# PointController.net
KiCad netlist of a schematic drawn in EAGLE
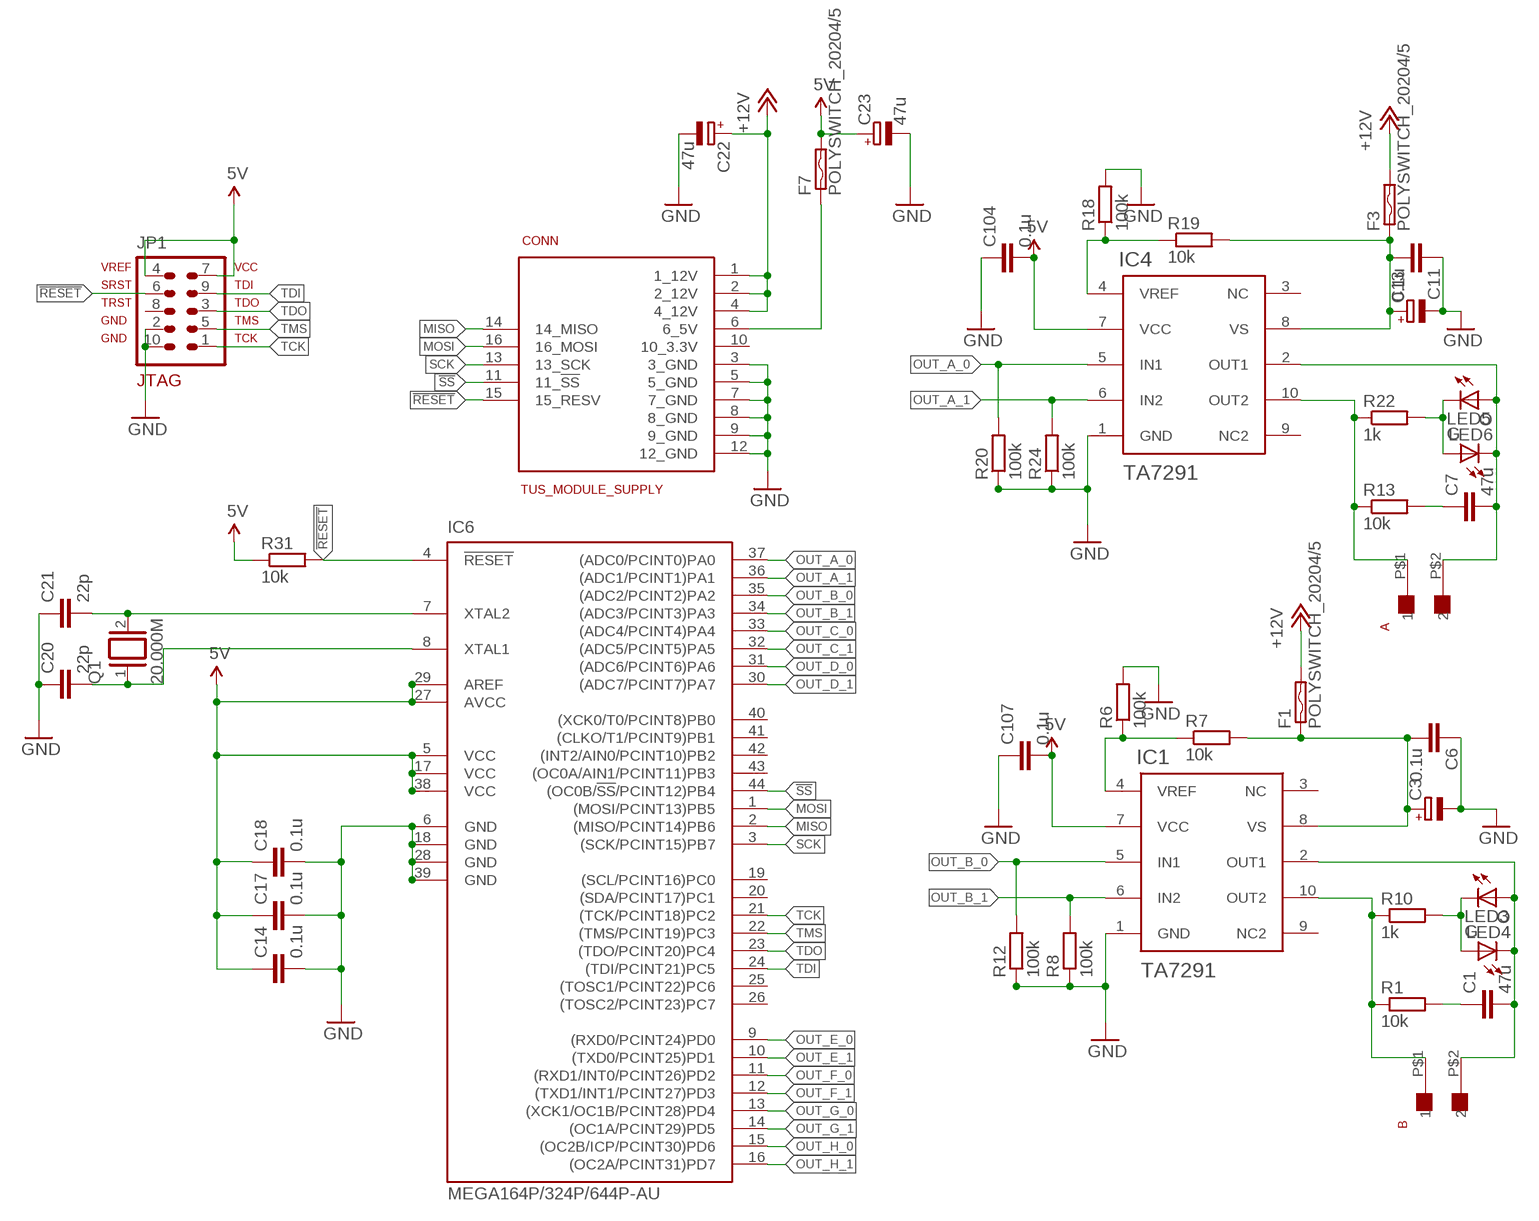
[diagram p0: schematic, sheet 1, part 1 of 2]
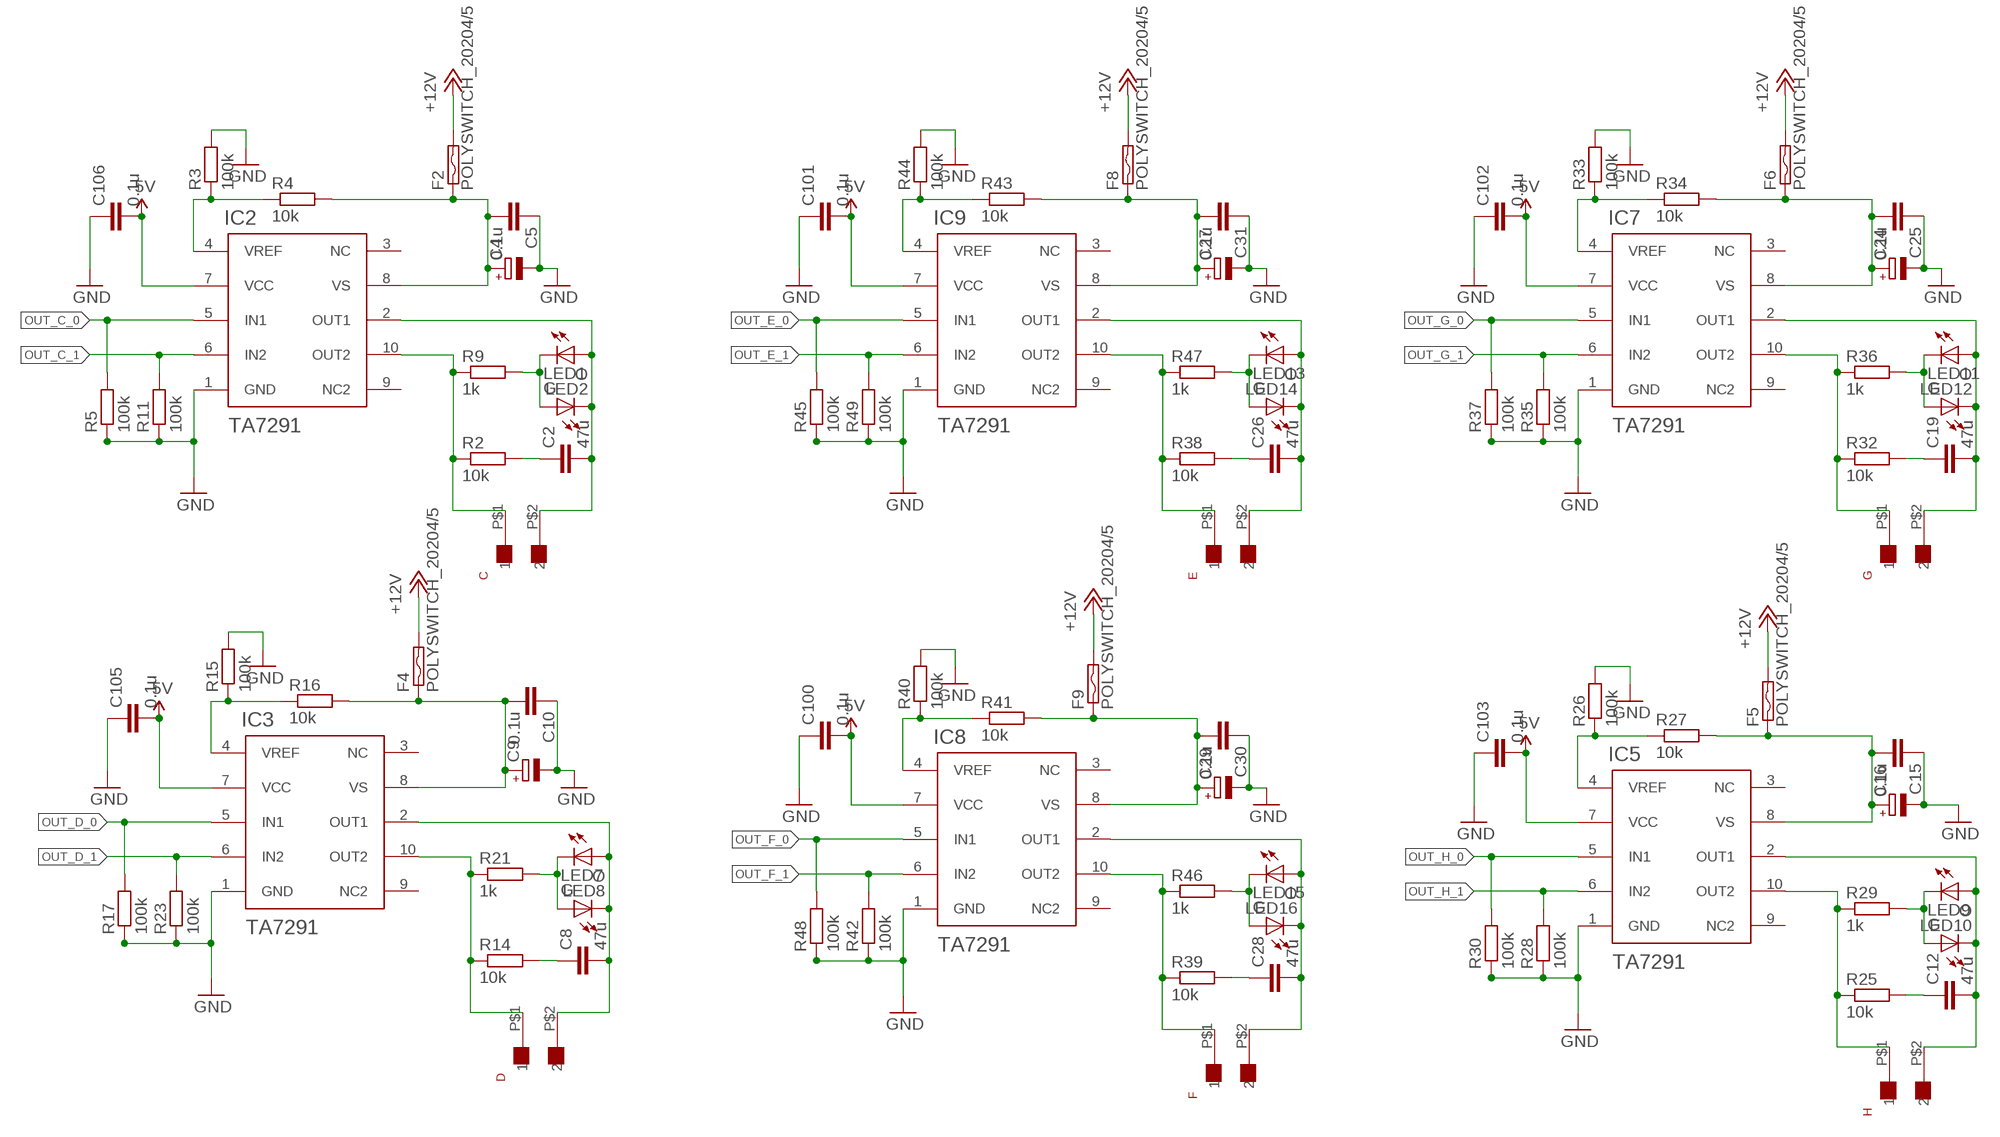
[diagram p1: schematic, sheet 1, part 2 of 2]

(export (version "E")
  (design (tool "Eeschema 10.0.6"))
  (components
    (comp (ref "A")
      (value "XH-2")
      (footprint "eagle-import:XH-2")
      (libsource (lib "eagle-import") (part "XH-2"))
    )
    (comp (ref "B")
      (value "XH-2")
      (footprint "eagle-import:XH-2")
      (libsource (lib "eagle-import") (part "XH-2"))
    )
    (comp (ref "C")
      (value "XH-2")
      (footprint "eagle-import:XH-2")
      (libsource (lib "eagle-import") (part "XH-2"))
    )
    (comp (ref "C1")
      (value "47u")
      (footprint "eagle-import:C5B3")
      (libsource (lib "eagle-import") (part "C5/3"))
    )
    (comp (ref "C2")
      (value "47u")
      (footprint "eagle-import:C5B3")
      (libsource (lib "eagle-import") (part "C5/3"))
    )
    (comp (ref "C3")
      (value "CPOL-EUE2.5-5")
      (footprint "eagle-import:E2,5-5")
      (libsource (lib "eagle-import") (part "CPOL-EUE2.5-5"))
    )
    (comp (ref "C4")
      (value "CPOL-EUE2.5-5")
      (footprint "eagle-import:E2,5-5")
      (libsource (lib "eagle-import") (part "CPOL-EUE2.5-5"))
    )
    (comp (ref "C5")
      (value "0.1u")
      (footprint "eagle-import:C1608")
      (libsource (lib "eagle-import") (part "C-EUC1608"))
    )
    (comp (ref "C6")
      (value "0.1u")
      (footprint "eagle-import:C1608")
      (libsource (lib "eagle-import") (part "C-EUC1608"))
    )
    (comp (ref "C7")
      (value "47u")
      (footprint "eagle-import:C5B3")
      (libsource (lib "eagle-import") (part "C5/3"))
    )
    (comp (ref "C8")
      (value "47u")
      (footprint "eagle-import:C5B3")
      (libsource (lib "eagle-import") (part "C5/3"))
    )
    (comp (ref "C9")
      (value "CPOL-EUE2.5-5")
      (footprint "eagle-import:E2,5-5")
      (libsource (lib "eagle-import") (part "CPOL-EUE2.5-5"))
    )
    (comp (ref "C10")
      (value "0.1u")
      (footprint "eagle-import:C1608")
      (libsource (lib "eagle-import") (part "C-EUC1608"))
    )
    (comp (ref "C11")
      (value "0.1u")
      (footprint "eagle-import:C1608")
      (libsource (lib "eagle-import") (part "C-EUC1608"))
    )
    (comp (ref "C12")
      (value "47u")
      (footprint "eagle-import:C5B3")
      (libsource (lib "eagle-import") (part "C5/3"))
    )
    (comp (ref "C13")
      (value "CPOL-EUE2.5-5")
      (footprint "eagle-import:E2,5-5")
      (libsource (lib "eagle-import") (part "CPOL-EUE2.5-5"))
    )
    (comp (ref "C14")
      (value "0.1u")
      (footprint "eagle-import:C1608")
      (libsource (lib "eagle-import") (part "C-EUC1608"))
    )
    (comp (ref "C15")
      (value "0.1u")
      (footprint "eagle-import:C1608")
      (libsource (lib "eagle-import") (part "C-EUC1608"))
    )
    (comp (ref "C16")
      (value "CPOL-EUE2.5-5")
      (footprint "eagle-import:E2,5-5")
      (libsource (lib "eagle-import") (part "CPOL-EUE2.5-5"))
    )
    (comp (ref "C17")
      (value "0.1u")
      (footprint "eagle-import:C1608")
      (libsource (lib "eagle-import") (part "C-EUC1608"))
    )
    (comp (ref "C18")
      (value "0.1u")
      (footprint "eagle-import:C1608")
      (libsource (lib "eagle-import") (part "C-EUC1608"))
    )
    (comp (ref "C19")
      (value "47u")
      (footprint "eagle-import:C5B3")
      (libsource (lib "eagle-import") (part "C5/3"))
    )
    (comp (ref "C20")
      (value "22p")
      (footprint "eagle-import:C1608")
      (libsource (lib "eagle-import") (part "C-EUC1608"))
    )
    (comp (ref "C21")
      (value "22p")
      (footprint "eagle-import:C1608")
      (libsource (lib "eagle-import") (part "C-EUC1608"))
    )
    (comp (ref "C22")
      (value "47u")
      (footprint "eagle-import:E2,5-5")
      (libsource (lib "eagle-import") (part "CPOL-EUE2.5-5"))
    )
    (comp (ref "C23")
      (value "47u")
      (footprint "eagle-import:E2,5-5")
      (libsource (lib "eagle-import") (part "CPOL-EUE2.5-5"))
    )
    (comp (ref "C24")
      (value "CPOL-EUE2.5-5")
      (footprint "eagle-import:E2,5-5")
      (libsource (lib "eagle-import") (part "CPOL-EUE2.5-5"))
    )
    (comp (ref "C25")
      (value "0.1u")
      (footprint "eagle-import:C1608")
      (libsource (lib "eagle-import") (part "C-EUC1608"))
    )
    (comp (ref "C26")
      (value "47u")
      (footprint "eagle-import:C5B3")
      (libsource (lib "eagle-import") (part "C5/3"))
    )
    (comp (ref "C27")
      (value "CPOL-EUE2.5-5")
      (footprint "eagle-import:E2,5-5")
      (libsource (lib "eagle-import") (part "CPOL-EUE2.5-5"))
    )
    (comp (ref "C28")
      (value "47u")
      (footprint "eagle-import:C5B3")
      (libsource (lib "eagle-import") (part "C5/3"))
    )
    (comp (ref "C29")
      (value "CPOL-EUE2.5-5")
      (footprint "eagle-import:E2,5-5")
      (libsource (lib "eagle-import") (part "CPOL-EUE2.5-5"))
    )
    (comp (ref "C30")
      (value "0.1u")
      (footprint "eagle-import:C1608")
      (libsource (lib "eagle-import") (part "C-EUC1608"))
    )
    (comp (ref "C31")
      (value "0.1u")
      (footprint "eagle-import:C1608")
      (libsource (lib "eagle-import") (part "C-EUC1608"))
    )
    (comp (ref "C100")
      (value "0.1u")
      (footprint "eagle-import:C1608")
      (libsource (lib "eagle-import") (part "C-EUC1608"))
    )
    (comp (ref "C101")
      (value "0.1u")
      (footprint "eagle-import:C1608")
      (libsource (lib "eagle-import") (part "C-EUC1608"))
    )
    (comp (ref "C102")
      (value "0.1u")
      (footprint "eagle-import:C1608")
      (libsource (lib "eagle-import") (part "C-EUC1608"))
    )
    (comp (ref "C103")
      (value "0.1u")
      (footprint "eagle-import:C1608")
      (libsource (lib "eagle-import") (part "C-EUC1608"))
    )
    (comp (ref "C104")
      (value "0.1u")
      (footprint "eagle-import:C1608")
      (libsource (lib "eagle-import") (part "C-EUC1608"))
    )
    (comp (ref "C105")
      (value "0.1u")
      (footprint "eagle-import:C1608")
      (libsource (lib "eagle-import") (part "C-EUC1608"))
    )
    (comp (ref "C106")
      (value "0.1u")
      (footprint "eagle-import:C1608")
      (libsource (lib "eagle-import") (part "C-EUC1608"))
    )
    (comp (ref "C107")
      (value "0.1u")
      (footprint "eagle-import:C1608")
      (libsource (lib "eagle-import") (part "C-EUC1608"))
    )
    (comp (ref "CONN")
      (value "TUS_MODULE_SUPPLY")
      (footprint "eagle-import:2X08")
      (libsource (lib "eagle-import") (part "TUS_MODULE_SUPPLY"))
    )
    (comp (ref "D")
      (value "XH-2")
      (footprint "eagle-import:XH-2")
      (libsource (lib "eagle-import") (part "XH-2"))
    )
    (comp (ref "E")
      (value "XH-2")
      (footprint "eagle-import:XH-2")
      (libsource (lib "eagle-import") (part "XH-2"))
    )
    (comp (ref "F")
      (value "XH-2")
      (footprint "eagle-import:XH-2")
      (libsource (lib "eagle-import") (part "XH-2"))
    )
    (comp (ref "F1")
      (value "POLYSWITCH_20204/5")
      (footprint "eagle-import:0204_5")
      (libsource (lib "eagle-import") (part "POLYSWITCH_20204/5"))
    )
    (comp (ref "F2")
      (value "POLYSWITCH_20204/5")
      (footprint "eagle-import:0204_5")
      (libsource (lib "eagle-import") (part "POLYSWITCH_20204/5"))
    )
    (comp (ref "F3")
      (value "POLYSWITCH_20204/5")
      (footprint "eagle-import:0204_5")
      (libsource (lib "eagle-import") (part "POLYSWITCH_20204/5"))
    )
    (comp (ref "F4")
      (value "POLYSWITCH_20204/5")
      (footprint "eagle-import:0204_5")
      (libsource (lib "eagle-import") (part "POLYSWITCH_20204/5"))
    )
    (comp (ref "F5")
      (value "POLYSWITCH_20204/5")
      (footprint "eagle-import:0204_5")
      (libsource (lib "eagle-import") (part "POLYSWITCH_20204/5"))
    )
    (comp (ref "F6")
      (value "POLYSWITCH_20204/5")
      (footprint "eagle-import:0204_5")
      (libsource (lib "eagle-import") (part "POLYSWITCH_20204/5"))
    )
    (comp (ref "F7")
      (value "POLYSWITCH_20204/5")
      (footprint "eagle-import:0204_5")
      (libsource (lib "eagle-import") (part "POLYSWITCH_20204/5"))
    )
    (comp (ref "F8")
      (value "POLYSWITCH_20204/5")
      (footprint "eagle-import:0204_5")
      (libsource (lib "eagle-import") (part "POLYSWITCH_20204/5"))
    )
    (comp (ref "F9")
      (value "POLYSWITCH_20204/5")
      (footprint "eagle-import:0204_5")
      (libsource (lib "eagle-import") (part "POLYSWITCH_20204/5"))
    )
    (comp (ref "G")
      (value "XH-2")
      (footprint "eagle-import:XH-2")
      (libsource (lib "eagle-import") (part "XH-2"))
    )
    (comp (ref "H")
      (value "XH-2")
      (footprint "eagle-import:XH-2")
      (libsource (lib "eagle-import") (part "XH-2"))
    )
    (comp (ref "IC1")
      (value "TA7291")
      (footprint "eagle-import:HSIP10")
      (libsource (lib "eagle-import") (part "TA7291"))
    )
    (comp (ref "IC2")
      (value "TA7291")
      (footprint "eagle-import:HSIP10")
      (libsource (lib "eagle-import") (part "TA7291"))
    )
    (comp (ref "IC3")
      (value "TA7291")
      (footprint "eagle-import:HSIP10")
      (libsource (lib "eagle-import") (part "TA7291"))
    )
    (comp (ref "IC4")
      (value "TA7291")
      (footprint "eagle-import:HSIP10")
      (libsource (lib "eagle-import") (part "TA7291"))
    )
    (comp (ref "IC5")
      (value "TA7291")
      (footprint "eagle-import:HSIP10")
      (libsource (lib "eagle-import") (part "TA7291"))
    )
    (comp (ref "IC6")
      (value "MEGA164P/324P/644P-AU")
      (footprint "eagle-import:TQFP44")
      (libsource (lib "eagle-import") (part "MEGA164P/324P/644P-AU"))
    )
    (comp (ref "IC7")
      (value "TA7291")
      (footprint "eagle-import:HSIP10")
      (libsource (lib "eagle-import") (part "TA7291"))
    )
    (comp (ref "IC8")
      (value "TA7291")
      (footprint "eagle-import:HSIP10")
      (libsource (lib "eagle-import") (part "TA7291"))
    )
    (comp (ref "IC9")
      (value "TA7291")
      (footprint "eagle-import:HSIP10")
      (libsource (lib "eagle-import") (part "TA7291"))
    )
    (comp (ref "JP1")
      (value "AVR-JTAG-10")
      (footprint "eagle-import:AVR-JTAG-10")
      (libsource (lib "eagle-import") (part "AVR-JTAG-10"))
    )
    (comp (ref "LED1")
      (value "G")
      (footprint "eagle-import:LED3MM")
      (libsource (lib "eagle-import") (part "LED3MM"))
    )
    (comp (ref "LED2")
      (value "O")
      (footprint "eagle-import:LED3MM")
      (libsource (lib "eagle-import") (part "LED3MM"))
    )
    (comp (ref "LED3")
      (value "G")
      (footprint "eagle-import:LED3MM")
      (libsource (lib "eagle-import") (part "LED3MM"))
    )
    (comp (ref "LED4")
      (value "O")
      (footprint "eagle-import:LED3MM")
      (libsource (lib "eagle-import") (part "LED3MM"))
    )
    (comp (ref "LED5")
      (value "G")
      (footprint "eagle-import:LED3MM")
      (libsource (lib "eagle-import") (part "LED3MM"))
    )
    (comp (ref "LED6")
      (value "O")
      (footprint "eagle-import:LED3MM")
      (libsource (lib "eagle-import") (part "LED3MM"))
    )
    (comp (ref "LED7")
      (value "G")
      (footprint "eagle-import:LED3MM")
      (libsource (lib "eagle-import") (part "LED3MM"))
    )
    (comp (ref "LED8")
      (value "O")
      (footprint "eagle-import:LED3MM")
      (libsource (lib "eagle-import") (part "LED3MM"))
    )
    (comp (ref "LED9")
      (value "G")
      (footprint "eagle-import:LED3MM")
      (libsource (lib "eagle-import") (part "LED3MM"))
    )
    (comp (ref "LED10")
      (value "O")
      (footprint "eagle-import:LED3MM")
      (libsource (lib "eagle-import") (part "LED3MM"))
    )
    (comp (ref "LED11")
      (value "G")
      (footprint "eagle-import:LED3MM")
      (libsource (lib "eagle-import") (part "LED3MM"))
    )
    (comp (ref "LED12")
      (value "O")
      (footprint "eagle-import:LED3MM")
      (libsource (lib "eagle-import") (part "LED3MM"))
    )
    (comp (ref "LED13")
      (value "G")
      (footprint "eagle-import:LED3MM")
      (libsource (lib "eagle-import") (part "LED3MM"))
    )
    (comp (ref "LED14")
      (value "O")
      (footprint "eagle-import:LED3MM")
      (libsource (lib "eagle-import") (part "LED3MM"))
    )
    (comp (ref "LED15")
      (value "G")
      (footprint "eagle-import:LED3MM")
      (libsource (lib "eagle-import") (part "LED3MM"))
    )
    (comp (ref "LED16")
      (value "O")
      (footprint "eagle-import:LED3MM")
      (libsource (lib "eagle-import") (part "LED3MM"))
    )
    (comp (ref "Q1")
      (value "20.000M")
      (footprint "eagle-import:QS")
      (libsource (lib "eagle-import") (part "XTAL/S"))
    )
    (comp (ref "R1")
      (value "10k")
      (footprint "eagle-import:0204_7")
      (libsource (lib "eagle-import") (part "resistor_R-EU_0204/7"))
    )
    (comp (ref "R2")
      (value "10k")
      (footprint "eagle-import:0204_7")
      (libsource (lib "eagle-import") (part "resistor_R-EU_0204/7"))
    )
    (comp (ref "R3")
      (value "100k")
      (footprint "eagle-import:R0603")
      (libsource (lib "eagle-import") (part "R-EU_R0603"))
    )
    (comp (ref "R4")
      (value "10k")
      (footprint "eagle-import:R0603")
      (libsource (lib "eagle-import") (part "R-EU_R0603"))
    )
    (comp (ref "R5")
      (value "100k")
      (footprint "eagle-import:R0603")
      (libsource (lib "eagle-import") (part "R-EU_R0603"))
    )
    (comp (ref "R6")
      (value "100k")
      (footprint "eagle-import:R0603")
      (libsource (lib "eagle-import") (part "R-EU_R0603"))
    )
    (comp (ref "R7")
      (value "10k")
      (footprint "eagle-import:R0603")
      (libsource (lib "eagle-import") (part "R-EU_R0603"))
    )
    (comp (ref "R8")
      (value "100k")
      (footprint "eagle-import:R0603")
      (libsource (lib "eagle-import") (part "R-EU_R0603"))
    )
    (comp (ref "R9")
      (value "1k")
      (footprint "eagle-import:R0603")
      (libsource (lib "eagle-import") (part "resistor_R-EU_R0603"))
    )
    (comp (ref "R10")
      (value "1k")
      (footprint "eagle-import:R0603")
      (libsource (lib "eagle-import") (part "resistor_R-EU_R0603"))
    )
    (comp (ref "R11")
      (value "100k")
      (footprint "eagle-import:R0603")
      (libsource (lib "eagle-import") (part "R-EU_R0603"))
    )
    (comp (ref "R12")
      (value "100k")
      (footprint "eagle-import:R0603")
      (libsource (lib "eagle-import") (part "R-EU_R0603"))
    )
    (comp (ref "R13")
      (value "10k")
      (footprint "eagle-import:0204_7")
      (libsource (lib "eagle-import") (part "resistor_R-EU_0204/7"))
    )
    (comp (ref "R14")
      (value "10k")
      (footprint "eagle-import:0204_7")
      (libsource (lib "eagle-import") (part "resistor_R-EU_0204/7"))
    )
    (comp (ref "R15")
      (value "100k")
      (footprint "eagle-import:R0603")
      (libsource (lib "eagle-import") (part "R-EU_R0603"))
    )
    (comp (ref "R16")
      (value "10k")
      (footprint "eagle-import:R0603")
      (libsource (lib "eagle-import") (part "R-EU_R0603"))
    )
    (comp (ref "R17")
      (value "100k")
      (footprint "eagle-import:R0603")
      (libsource (lib "eagle-import") (part "R-EU_R0603"))
    )
    (comp (ref "R18")
      (value "100k")
      (footprint "eagle-import:R0603")
      (libsource (lib "eagle-import") (part "R-EU_R0603"))
    )
    (comp (ref "R19")
      (value "10k")
      (footprint "eagle-import:R0603")
      (libsource (lib "eagle-import") (part "R-EU_R0603"))
    )
    (comp (ref "R20")
      (value "100k")
      (footprint "eagle-import:R0603")
      (libsource (lib "eagle-import") (part "R-EU_R0603"))
    )
    (comp (ref "R21")
      (value "1k")
      (footprint "eagle-import:R0603")
      (libsource (lib "eagle-import") (part "resistor_R-EU_R0603"))
    )
    (comp (ref "R22")
      (value "1k")
      (footprint "eagle-import:R0603")
      (libsource (lib "eagle-import") (part "resistor_R-EU_R0603"))
    )
    (comp (ref "R23")
      (value "100k")
      (footprint "eagle-import:R0603")
      (libsource (lib "eagle-import") (part "R-EU_R0603"))
    )
    (comp (ref "R24")
      (value "100k")
      (footprint "eagle-import:R0603")
      (libsource (lib "eagle-import") (part "R-EU_R0603"))
    )
    (comp (ref "R25")
      (value "10k")
      (footprint "eagle-import:0204_7")
      (libsource (lib "eagle-import") (part "resistor_R-EU_0204/7"))
    )
    (comp (ref "R26")
      (value "100k")
      (footprint "eagle-import:R0603")
      (libsource (lib "eagle-import") (part "R-EU_R0603"))
    )
    (comp (ref "R27")
      (value "10k")
      (footprint "eagle-import:R0603")
      (libsource (lib "eagle-import") (part "R-EU_R0603"))
    )
    (comp (ref "R28")
      (value "100k")
      (footprint "eagle-import:R0603")
      (libsource (lib "eagle-import") (part "R-EU_R0603"))
    )
    (comp (ref "R29")
      (value "1k")
      (footprint "eagle-import:R0603")
      (libsource (lib "eagle-import") (part "resistor_R-EU_R0603"))
    )
    (comp (ref "R30")
      (value "100k")
      (footprint "eagle-import:R0603")
      (libsource (lib "eagle-import") (part "R-EU_R0603"))
    )
    (comp (ref "R31")
      (value "10k")
      (footprint "eagle-import:R0603")
      (libsource (lib "eagle-import") (part "R-EU_R0603"))
    )
    (comp (ref "R32")
      (value "10k")
      (footprint "eagle-import:0204_7")
      (libsource (lib "eagle-import") (part "resistor_R-EU_0204/7"))
    )
    (comp (ref "R33")
      (value "100k")
      (footprint "eagle-import:R0603")
      (libsource (lib "eagle-import") (part "R-EU_R0603"))
    )
    (comp (ref "R34")
      (value "10k")
      (footprint "eagle-import:R0603")
      (libsource (lib "eagle-import") (part "R-EU_R0603"))
    )
    (comp (ref "R35")
      (value "100k")
      (footprint "eagle-import:R0603")
      (libsource (lib "eagle-import") (part "R-EU_R0603"))
    )
    (comp (ref "R36")
      (value "1k")
      (footprint "eagle-import:R0603")
      (libsource (lib "eagle-import") (part "resistor_R-EU_R0603"))
    )
    (comp (ref "R37")
      (value "100k")
      (footprint "eagle-import:R0603")
      (libsource (lib "eagle-import") (part "R-EU_R0603"))
    )
    (comp (ref "R38")
      (value "10k")
      (footprint "eagle-import:0204_7")
      (libsource (lib "eagle-import") (part "resistor_R-EU_0204/7"))
    )
    (comp (ref "R39")
      (value "10k")
      (footprint "eagle-import:0204_7")
      (libsource (lib "eagle-import") (part "resistor_R-EU_0204/7"))
    )
    (comp (ref "R40")
      (value "100k")
      (footprint "eagle-import:R0603")
      (libsource (lib "eagle-import") (part "R-EU_R0603"))
    )
    (comp (ref "R41")
      (value "10k")
      (footprint "eagle-import:R0603")
      (libsource (lib "eagle-import") (part "R-EU_R0603"))
    )
    (comp (ref "R42")
      (value "100k")
      (footprint "eagle-import:R0603")
      (libsource (lib "eagle-import") (part "R-EU_R0603"))
    )
    (comp (ref "R43")
      (value "10k")
      (footprint "eagle-import:R0603")
      (libsource (lib "eagle-import") (part "R-EU_R0603"))
    )
    (comp (ref "R44")
      (value "100k")
      (footprint "eagle-import:R0603")
      (libsource (lib "eagle-import") (part "R-EU_R0603"))
    )
    (comp (ref "R45")
      (value "100k")
      (footprint "eagle-import:R0603")
      (libsource (lib "eagle-import") (part "R-EU_R0603"))
    )
    (comp (ref "R46")
      (value "1k")
      (footprint "eagle-import:R0603")
      (libsource (lib "eagle-import") (part "resistor_R-EU_R0603"))
    )
    (comp (ref "R47")
      (value "1k")
      (footprint "eagle-import:R0603")
      (libsource (lib "eagle-import") (part "resistor_R-EU_R0603"))
    )
    (comp (ref "R48")
      (value "100k")
      (footprint "eagle-import:R0603")
      (libsource (lib "eagle-import") (part "R-EU_R0603"))
    )
    (comp (ref "R49")
      (value "100k")
      (footprint "eagle-import:R0603")
      (libsource (lib "eagle-import") (part "R-EU_R0603"))
    )
  )
  (nets
    (net (code "1") (name "+12V") (class "Default")
      (node (ref "C22") (pin "+") (pinfunction "+_+") (pintype "passive"))
      (node (ref "CONN") (pin "1") (pinfunction "1_12V_1") (pintype "bidirectional"))
      (node (ref "CONN") (pin "2") (pinfunction "2_12V_2") (pintype "bidirectional"))
      (node (ref "CONN") (pin "4") (pinfunction "4_12V_4") (pintype "bidirectional"))
      (node (ref "F1") (pin "2") (pinfunction "2_2") (pintype "passive"))
      (node (ref "F2") (pin "2") (pinfunction "2_2") (pintype "passive"))
      (node (ref "F3") (pin "2") (pinfunction "2_2") (pintype "passive"))
      (node (ref "F4") (pin "2") (pinfunction "2_2") (pintype "passive"))
      (node (ref "F5") (pin "2") (pinfunction "2_2") (pintype "passive"))
      (node (ref "F6") (pin "2") (pinfunction "2_2") (pintype "passive"))
      (node (ref "F8") (pin "2") (pinfunction "2_2") (pintype "passive"))
      (node (ref "F9") (pin "2") (pinfunction "2_2") (pintype "passive"))
    )
    (net (code "2") (name "/~{RESET}") (class "Default")
      (node (ref "CONN") (pin "15") (pinfunction "15_RESV_15") (pintype "bidirectional"))
      (node (ref "IC6") (pin "4") (pinfunction "~{RESET}_4") (pintype "input"))
      (node (ref "JP1") (pin "6") (pinfunction "6_6") (pintype "passive"))
      (node (ref "R31") (pin "2") (pinfunction "2_2") (pintype "passive"))
    )
    (net (code "3") (name "/~{SS}") (class "Default")
      (node (ref "CONN") (pin "11") (pinfunction "11_~{SS}_11") (pintype "bidirectional"))
      (node (ref "IC6") (pin "44") (pinfunction "(OC0B/~{SS}/PCINT12)PB4_44") (pintype "bidirectional"))
    )
    (net (code "4") (name "5V") (class "Default")
      (node (ref "C100") (pin "2") (pinfunction "2_2") (pintype "passive"))
      (node (ref "C101") (pin "2") (pinfunction "2_2") (pintype "passive"))
      (node (ref "C102") (pin "2") (pinfunction "2_2") (pintype "passive"))
      (node (ref "C103") (pin "2") (pinfunction "2_2") (pintype "passive"))
      (node (ref "C104") (pin "2") (pinfunction "2_2") (pintype "passive"))
      (node (ref "C105") (pin "2") (pinfunction "2_2") (pintype "passive"))
      (node (ref "C106") (pin "2") (pinfunction "2_2") (pintype "passive"))
      (node (ref "C107") (pin "2") (pinfunction "2_2") (pintype "passive"))
      (node (ref "C14") (pin "1") (pinfunction "1_1") (pintype "passive"))
      (node (ref "C17") (pin "1") (pinfunction "1_1") (pintype "passive"))
      (node (ref "C18") (pin "1") (pinfunction "1_1") (pintype "passive"))
      (node (ref "C23") (pin "+") (pinfunction "+_+") (pintype "passive"))
      (node (ref "F7") (pin "2") (pinfunction "2_2") (pintype "passive"))
      (node (ref "IC1") (pin "7") (pinfunction "VCC_7") (pintype "bidirectional"))
      (node (ref "IC2") (pin "7") (pinfunction "VCC_7") (pintype "bidirectional"))
      (node (ref "IC3") (pin "7") (pinfunction "VCC_7") (pintype "bidirectional"))
      (node (ref "IC4") (pin "7") (pinfunction "VCC_7") (pintype "bidirectional"))
      (node (ref "IC5") (pin "7") (pinfunction "VCC_7") (pintype "bidirectional"))
      (node (ref "IC6") (pin "17") (pinfunction "VCC_17") (pintype "power_in"))
      (node (ref "IC6") (pin "27") (pinfunction "AVCC_27") (pintype "power_in"))
      (node (ref "IC6") (pin "29") (pinfunction "AREF_29") (pintype "power_in"))
      (node (ref "IC6") (pin "38") (pinfunction "VCC_38") (pintype "power_in"))
      (node (ref "IC6") (pin "5") (pinfunction "VCC_5") (pintype "power_in"))
      (node (ref "IC7") (pin "7") (pinfunction "VCC_7") (pintype "bidirectional"))
      (node (ref "IC8") (pin "7") (pinfunction "VCC_7") (pintype "bidirectional"))
      (node (ref "IC9") (pin "7") (pinfunction "VCC_7") (pintype "bidirectional"))
      (node (ref "JP1") (pin "4") (pinfunction "4_4") (pintype "passive"))
      (node (ref "JP1") (pin "7") (pinfunction "7_7") (pintype "passive"))
      (node (ref "R31") (pin "1") (pinfunction "1_1") (pintype "passive"))
    )
    (net (code "5") (name "GND") (class "Default")
      (node (ref "C10") (pin "1") (pinfunction "1_1") (pintype "passive"))
      (node (ref "C100") (pin "1") (pinfunction "1_1") (pintype "passive"))
      (node (ref "C101") (pin "1") (pinfunction "1_1") (pintype "passive"))
      (node (ref "C102") (pin "1") (pinfunction "1_1") (pintype "passive"))
      (node (ref "C103") (pin "1") (pinfunction "1_1") (pintype "passive"))
      (node (ref "C104") (pin "1") (pinfunction "1_1") (pintype "passive"))
      (node (ref "C105") (pin "1") (pinfunction "1_1") (pintype "passive"))
      (node (ref "C106") (pin "1") (pinfunction "1_1") (pintype "passive"))
      (node (ref "C107") (pin "1") (pinfunction "1_1") (pintype "passive"))
      (node (ref "C11") (pin "1") (pinfunction "1_1") (pintype "passive"))
      (node (ref "C13") (pin "-") (pinfunction "-_-") (pintype "passive"))
      (node (ref "C14") (pin "2") (pinfunction "2_2") (pintype "passive"))
      (node (ref "C15") (pin "1") (pinfunction "1_1") (pintype "passive"))
      (node (ref "C16") (pin "-") (pinfunction "-_-") (pintype "passive"))
      (node (ref "C17") (pin "2") (pinfunction "2_2") (pintype "passive"))
      (node (ref "C18") (pin "2") (pinfunction "2_2") (pintype "passive"))
      (node (ref "C20") (pin "1") (pinfunction "1_1") (pintype "passive"))
      (node (ref "C21") (pin "1") (pinfunction "1_1") (pintype "passive"))
      (node (ref "C22") (pin "-") (pinfunction "-_-") (pintype "passive"))
      (node (ref "C23") (pin "-") (pinfunction "-_-") (pintype "passive"))
      (node (ref "C24") (pin "-") (pinfunction "-_-") (pintype "passive"))
      (node (ref "C25") (pin "1") (pinfunction "1_1") (pintype "passive"))
      (node (ref "C27") (pin "-") (pinfunction "-_-") (pintype "passive"))
      (node (ref "C29") (pin "-") (pinfunction "-_-") (pintype "passive"))
      (node (ref "C3") (pin "-") (pinfunction "-_-") (pintype "passive"))
      (node (ref "C30") (pin "1") (pinfunction "1_1") (pintype "passive"))
      (node (ref "C31") (pin "1") (pinfunction "1_1") (pintype "passive"))
      (node (ref "C4") (pin "-") (pinfunction "-_-") (pintype "passive"))
      (node (ref "C5") (pin "1") (pinfunction "1_1") (pintype "passive"))
      (node (ref "C6") (pin "1") (pinfunction "1_1") (pintype "passive"))
      (node (ref "C9") (pin "-") (pinfunction "-_-") (pintype "passive"))
      (node (ref "CONN") (pin "12") (pinfunction "12_GND_12") (pintype "bidirectional"))
      (node (ref "CONN") (pin "3") (pinfunction "3_GND_3") (pintype "bidirectional"))
      (node (ref "CONN") (pin "5") (pinfunction "5_GND_5") (pintype "bidirectional"))
      (node (ref "CONN") (pin "7") (pinfunction "7_GND_7") (pintype "bidirectional"))
      (node (ref "CONN") (pin "8") (pinfunction "8_GND_8") (pintype "bidirectional"))
      (node (ref "CONN") (pin "9") (pinfunction "9_GND_9") (pintype "bidirectional"))
      (node (ref "IC1") (pin "1") (pinfunction "GND_1") (pintype "bidirectional"))
      (node (ref "IC2") (pin "1") (pinfunction "GND_1") (pintype "bidirectional"))
      (node (ref "IC3") (pin "1") (pinfunction "GND_1") (pintype "bidirectional"))
      (node (ref "IC4") (pin "1") (pinfunction "GND_1") (pintype "bidirectional"))
      (node (ref "IC5") (pin "1") (pinfunction "GND_1") (pintype "bidirectional"))
      (node (ref "IC6") (pin "18") (pinfunction "GND_18") (pintype "power_in"))
      (node (ref "IC6") (pin "28") (pinfunction "GND_28") (pintype "power_in"))
      (node (ref "IC6") (pin "39") (pinfunction "GND_39") (pintype "power_in"))
      (node (ref "IC6") (pin "6") (pinfunction "GND_6") (pintype "power_in"))
      (node (ref "IC7") (pin "1") (pinfunction "GND_1") (pintype "bidirectional"))
      (node (ref "IC8") (pin "1") (pinfunction "GND_1") (pintype "bidirectional"))
      (node (ref "IC9") (pin "1") (pinfunction "GND_1") (pintype "bidirectional"))
      (node (ref "JP1") (pin "10") (pinfunction "10_10") (pintype "passive"))
      (node (ref "JP1") (pin "2") (pinfunction "2_2") (pintype "passive"))
      (node (ref "R11") (pin "1") (pinfunction "1_1") (pintype "passive"))
      (node (ref "R12") (pin "1") (pinfunction "1_1") (pintype "passive"))
      (node (ref "R15") (pin "2") (pinfunction "2_2") (pintype "passive"))
      (node (ref "R17") (pin "1") (pinfunction "1_1") (pintype "passive"))
      (node (ref "R18") (pin "2") (pinfunction "2_2") (pintype "passive"))
      (node (ref "R20") (pin "1") (pinfunction "1_1") (pintype "passive"))
      (node (ref "R23") (pin "1") (pinfunction "1_1") (pintype "passive"))
      (node (ref "R24") (pin "1") (pinfunction "1_1") (pintype "passive"))
      (node (ref "R26") (pin "2") (pinfunction "2_2") (pintype "passive"))
      (node (ref "R28") (pin "1") (pinfunction "1_1") (pintype "passive"))
      (node (ref "R3") (pin "2") (pinfunction "2_2") (pintype "passive"))
      (node (ref "R30") (pin "1") (pinfunction "1_1") (pintype "passive"))
      (node (ref "R33") (pin "2") (pinfunction "2_2") (pintype "passive"))
      (node (ref "R35") (pin "1") (pinfunction "1_1") (pintype "passive"))
      (node (ref "R37") (pin "1") (pinfunction "1_1") (pintype "passive"))
      (node (ref "R40") (pin "2") (pinfunction "2_2") (pintype "passive"))
      (node (ref "R42") (pin "1") (pinfunction "1_1") (pintype "passive"))
      (node (ref "R44") (pin "2") (pinfunction "2_2") (pintype "passive"))
      (node (ref "R45") (pin "1") (pinfunction "1_1") (pintype "passive"))
      (node (ref "R48") (pin "1") (pinfunction "1_1") (pintype "passive"))
      (node (ref "R49") (pin "1") (pinfunction "1_1") (pintype "passive"))
      (node (ref "R5") (pin "1") (pinfunction "1_1") (pintype "passive"))
      (node (ref "R6") (pin "2") (pinfunction "2_2") (pintype "passive"))
      (node (ref "R8") (pin "1") (pinfunction "1_1") (pintype "passive"))
    )
    (net (code "6") (name "MISO") (class "Default")
      (node (ref "CONN") (pin "14") (pinfunction "14_MISO_14") (pintype "bidirectional"))
      (node (ref "IC6") (pin "2") (pinfunction "(MISO/PCINT14)PB6_2") (pintype "bidirectional"))
    )
    (net (code "7") (name "MOSI") (class "Default")
      (node (ref "CONN") (pin "16") (pinfunction "16_MOSI_16") (pintype "bidirectional"))
      (node (ref "IC6") (pin "1") (pinfunction "(MOSI/PCINT13)PB5_1") (pintype "bidirectional"))
    )
    (net (code "8") (name "Net-(A-1)") (class "Default")
      (node (ref "A") (pin "P$1") (pinfunction "1_P$1") (pintype "bidirectional"))
      (node (ref "IC4") (pin "10") (pinfunction "OUT2_10") (pintype "bidirectional"))
      (node (ref "R13") (pin "1") (pinfunction "1_1") (pintype "passive"))
      (node (ref "R22") (pin "1") (pinfunction "1_1") (pintype "passive"))
    )
    (net (code "9") (name "Net-(A-2)") (class "Default")
      (node (ref "A") (pin "P$2") (pinfunction "2_P$2") (pintype "bidirectional"))
      (node (ref "C7") (pin "2") (pinfunction "2_2") (pintype "passive"))
      (node (ref "IC4") (pin "2") (pinfunction "OUT1_2") (pintype "bidirectional"))
      (node (ref "LED5") (pin "A") (pinfunction "A_A") (pintype "passive"))
      (node (ref "LED6") (pin "K") (pinfunction "C_K") (pintype "passive"))
    )
    (net (code "10") (name "Net-(B-1)") (class "Default")
      (node (ref "B") (pin "P$1") (pinfunction "1_P$1") (pintype "bidirectional"))
      (node (ref "IC1") (pin "10") (pinfunction "OUT2_10") (pintype "bidirectional"))
      (node (ref "R1") (pin "1") (pinfunction "1_1") (pintype "passive"))
      (node (ref "R10") (pin "1") (pinfunction "1_1") (pintype "passive"))
    )
    (net (code "11") (name "Net-(B-2)") (class "Default")
      (node (ref "B") (pin "P$2") (pinfunction "2_P$2") (pintype "bidirectional"))
      (node (ref "C1") (pin "2") (pinfunction "2_2") (pintype "passive"))
      (node (ref "IC1") (pin "2") (pinfunction "OUT1_2") (pintype "bidirectional"))
      (node (ref "LED3") (pin "A") (pinfunction "A_A") (pintype "passive"))
      (node (ref "LED4") (pin "K") (pinfunction "C_K") (pintype "passive"))
    )
    (net (code "12") (name "Net-(C-1)") (class "Default")
      (node (ref "C") (pin "P$1") (pinfunction "1_P$1") (pintype "bidirectional"))
      (node (ref "IC2") (pin "10") (pinfunction "OUT2_10") (pintype "bidirectional"))
      (node (ref "R2") (pin "1") (pinfunction "1_1") (pintype "passive"))
      (node (ref "R9") (pin "1") (pinfunction "1_1") (pintype "passive"))
    )
    (net (code "13") (name "Net-(C-2)") (class "Default")
      (node (ref "C") (pin "P$2") (pinfunction "2_P$2") (pintype "bidirectional"))
      (node (ref "C2") (pin "2") (pinfunction "2_2") (pintype "passive"))
      (node (ref "IC2") (pin "2") (pinfunction "OUT1_2") (pintype "bidirectional"))
      (node (ref "LED1") (pin "A") (pinfunction "A_A") (pintype "passive"))
      (node (ref "LED2") (pin "K") (pinfunction "C_K") (pintype "passive"))
    )
    (net (code "14") (name "Net-(C1-Pad1)") (class "Default")
      (node (ref "C1") (pin "1") (pinfunction "1_1") (pintype "passive"))
      (node (ref "R1") (pin "2") (pinfunction "2_2") (pintype "passive"))
    )
    (net (code "15") (name "Net-(C2-Pad1)") (class "Default")
      (node (ref "C2") (pin "1") (pinfunction "1_1") (pintype "passive"))
      (node (ref "R2") (pin "2") (pinfunction "2_2") (pintype "passive"))
    )
    (net (code "16") (name "Net-(C7-Pad1)") (class "Default")
      (node (ref "C7") (pin "1") (pinfunction "1_1") (pintype "passive"))
      (node (ref "R13") (pin "2") (pinfunction "2_2") (pintype "passive"))
    )
    (net (code "17") (name "Net-(C8-Pad1)") (class "Default")
      (node (ref "C8") (pin "1") (pinfunction "1_1") (pintype "passive"))
      (node (ref "R14") (pin "2") (pinfunction "2_2") (pintype "passive"))
    )
    (net (code "18") (name "Net-(C12-Pad1)") (class "Default")
      (node (ref "C12") (pin "1") (pinfunction "1_1") (pintype "passive"))
      (node (ref "R25") (pin "2") (pinfunction "2_2") (pintype "passive"))
    )
    (net (code "19") (name "Net-(C19-Pad1)") (class "Default")
      (node (ref "C19") (pin "1") (pinfunction "1_1") (pintype "passive"))
      (node (ref "R32") (pin "2") (pinfunction "2_2") (pintype "passive"))
    )
    (net (code "20") (name "Net-(C26-Pad1)") (class "Default")
      (node (ref "C26") (pin "1") (pinfunction "1_1") (pintype "passive"))
      (node (ref "R38") (pin "2") (pinfunction "2_2") (pintype "passive"))
    )
    (net (code "21") (name "Net-(C28-Pad1)") (class "Default")
      (node (ref "C28") (pin "1") (pinfunction "1_1") (pintype "passive"))
      (node (ref "R39") (pin "2") (pinfunction "2_2") (pintype "passive"))
    )
    (net (code "22") (name "Net-(CONN-6_5V)") (class "Default")
      (node (ref "CONN") (pin "6") (pinfunction "6_5V_6") (pintype "bidirectional"))
      (node (ref "F7") (pin "1") (pinfunction "1_1") (pintype "passive"))
    )
    (net (code "23") (name "Net-(D-1)") (class "Default")
      (node (ref "D") (pin "P$1") (pinfunction "1_P$1") (pintype "bidirectional"))
      (node (ref "IC3") (pin "10") (pinfunction "OUT2_10") (pintype "bidirectional"))
      (node (ref "R14") (pin "1") (pinfunction "1_1") (pintype "passive"))
      (node (ref "R21") (pin "1") (pinfunction "1_1") (pintype "passive"))
    )
    (net (code "24") (name "Net-(D-2)") (class "Default")
      (node (ref "C8") (pin "2") (pinfunction "2_2") (pintype "passive"))
      (node (ref "D") (pin "P$2") (pinfunction "2_P$2") (pintype "bidirectional"))
      (node (ref "IC3") (pin "2") (pinfunction "OUT1_2") (pintype "bidirectional"))
      (node (ref "LED7") (pin "A") (pinfunction "A_A") (pintype "passive"))
      (node (ref "LED8") (pin "K") (pinfunction "C_K") (pintype "passive"))
    )
    (net (code "25") (name "Net-(E-1)") (class "Default")
      (node (ref "E") (pin "P$1") (pinfunction "1_P$1") (pintype "bidirectional"))
      (node (ref "IC9") (pin "10") (pinfunction "OUT2_10") (pintype "bidirectional"))
      (node (ref "R38") (pin "1") (pinfunction "1_1") (pintype "passive"))
      (node (ref "R47") (pin "1") (pinfunction "1_1") (pintype "passive"))
    )
    (net (code "26") (name "Net-(E-2)") (class "Default")
      (node (ref "C26") (pin "2") (pinfunction "2_2") (pintype "passive"))
      (node (ref "E") (pin "P$2") (pinfunction "2_P$2") (pintype "bidirectional"))
      (node (ref "IC9") (pin "2") (pinfunction "OUT1_2") (pintype "bidirectional"))
      (node (ref "LED13") (pin "A") (pinfunction "A_A") (pintype "passive"))
      (node (ref "LED14") (pin "K") (pinfunction "C_K") (pintype "passive"))
    )
    (net (code "27") (name "Net-(F-1)") (class "Default")
      (node (ref "F") (pin "P$1") (pinfunction "1_P$1") (pintype "bidirectional"))
      (node (ref "IC8") (pin "10") (pinfunction "OUT2_10") (pintype "bidirectional"))
      (node (ref "R39") (pin "1") (pinfunction "1_1") (pintype "passive"))
      (node (ref "R46") (pin "1") (pinfunction "1_1") (pintype "passive"))
    )
    (net (code "28") (name "Net-(F-2)") (class "Default")
      (node (ref "C28") (pin "2") (pinfunction "2_2") (pintype "passive"))
      (node (ref "F") (pin "P$2") (pinfunction "2_P$2") (pintype "bidirectional"))
      (node (ref "IC8") (pin "2") (pinfunction "OUT1_2") (pintype "bidirectional"))
      (node (ref "LED15") (pin "A") (pinfunction "A_A") (pintype "passive"))
      (node (ref "LED16") (pin "K") (pinfunction "C_K") (pintype "passive"))
    )
    (net (code "29") (name "Net-(G-1)") (class "Default")
      (node (ref "G") (pin "P$1") (pinfunction "1_P$1") (pintype "bidirectional"))
      (node (ref "IC7") (pin "10") (pinfunction "OUT2_10") (pintype "bidirectional"))
      (node (ref "R32") (pin "1") (pinfunction "1_1") (pintype "passive"))
      (node (ref "R36") (pin "1") (pinfunction "1_1") (pintype "passive"))
    )
    (net (code "30") (name "Net-(G-2)") (class "Default")
      (node (ref "C19") (pin "2") (pinfunction "2_2") (pintype "passive"))
      (node (ref "G") (pin "P$2") (pinfunction "2_P$2") (pintype "bidirectional"))
      (node (ref "IC7") (pin "2") (pinfunction "OUT1_2") (pintype "bidirectional"))
      (node (ref "LED11") (pin "A") (pinfunction "A_A") (pintype "passive"))
      (node (ref "LED12") (pin "K") (pinfunction "C_K") (pintype "passive"))
    )
    (net (code "31") (name "Net-(H-1)") (class "Default")
      (node (ref "H") (pin "P$1") (pinfunction "1_P$1") (pintype "bidirectional"))
      (node (ref "IC5") (pin "10") (pinfunction "OUT2_10") (pintype "bidirectional"))
      (node (ref "R25") (pin "1") (pinfunction "1_1") (pintype "passive"))
      (node (ref "R29") (pin "1") (pinfunction "1_1") (pintype "passive"))
    )
    (net (code "32") (name "Net-(H-2)") (class "Default")
      (node (ref "C12") (pin "2") (pinfunction "2_2") (pintype "passive"))
      (node (ref "H") (pin "P$2") (pinfunction "2_P$2") (pintype "bidirectional"))
      (node (ref "IC5") (pin "2") (pinfunction "OUT1_2") (pintype "bidirectional"))
      (node (ref "LED10") (pin "K") (pinfunction "C_K") (pintype "passive"))
      (node (ref "LED9") (pin "A") (pinfunction "A_A") (pintype "passive"))
    )
    (net (code "33") (name "Net-(IC1-VREF)") (class "Default")
      (node (ref "IC1") (pin "4") (pinfunction "VREF_4") (pintype "bidirectional"))
      (node (ref "R6") (pin "1") (pinfunction "1_1") (pintype "passive"))
      (node (ref "R7") (pin "1") (pinfunction "1_1") (pintype "passive"))
    )
    (net (code "34") (name "Net-(IC1-VS)") (class "Default")
      (node (ref "C3") (pin "+") (pinfunction "+_+") (pintype "passive"))
      (node (ref "C6") (pin "2") (pinfunction "2_2") (pintype "passive"))
      (node (ref "F1") (pin "1") (pinfunction "1_1") (pintype "passive"))
      (node (ref "IC1") (pin "8") (pinfunction "VS_8") (pintype "bidirectional"))
      (node (ref "R7") (pin "2") (pinfunction "2_2") (pintype "passive"))
    )
    (net (code "35") (name "Net-(IC2-VREF)") (class "Default")
      (node (ref "IC2") (pin "4") (pinfunction "VREF_4") (pintype "bidirectional"))
      (node (ref "R3") (pin "1") (pinfunction "1_1") (pintype "passive"))
      (node (ref "R4") (pin "1") (pinfunction "1_1") (pintype "passive"))
    )
    (net (code "36") (name "Net-(IC2-VS)") (class "Default")
      (node (ref "C4") (pin "+") (pinfunction "+_+") (pintype "passive"))
      (node (ref "C5") (pin "2") (pinfunction "2_2") (pintype "passive"))
      (node (ref "F2") (pin "1") (pinfunction "1_1") (pintype "passive"))
      (node (ref "IC2") (pin "8") (pinfunction "VS_8") (pintype "bidirectional"))
      (node (ref "R4") (pin "2") (pinfunction "2_2") (pintype "passive"))
    )
    (net (code "37") (name "Net-(IC3-VREF)") (class "Default")
      (node (ref "IC3") (pin "4") (pinfunction "VREF_4") (pintype "bidirectional"))
      (node (ref "R15") (pin "1") (pinfunction "1_1") (pintype "passive"))
      (node (ref "R16") (pin "1") (pinfunction "1_1") (pintype "passive"))
    )
    (net (code "38") (name "Net-(IC3-VS)") (class "Default")
      (node (ref "C10") (pin "2") (pinfunction "2_2") (pintype "passive"))
      (node (ref "C9") (pin "+") (pinfunction "+_+") (pintype "passive"))
      (node (ref "F4") (pin "1") (pinfunction "1_1") (pintype "passive"))
      (node (ref "IC3") (pin "8") (pinfunction "VS_8") (pintype "bidirectional"))
      (node (ref "R16") (pin "2") (pinfunction "2_2") (pintype "passive"))
    )
    (net (code "39") (name "Net-(IC4-VREF)") (class "Default")
      (node (ref "IC4") (pin "4") (pinfunction "VREF_4") (pintype "bidirectional"))
      (node (ref "R18") (pin "1") (pinfunction "1_1") (pintype "passive"))
      (node (ref "R19") (pin "1") (pinfunction "1_1") (pintype "passive"))
    )
    (net (code "40") (name "Net-(IC4-VS)") (class "Default")
      (node (ref "C11") (pin "2") (pinfunction "2_2") (pintype "passive"))
      (node (ref "C13") (pin "+") (pinfunction "+_+") (pintype "passive"))
      (node (ref "F3") (pin "1") (pinfunction "1_1") (pintype "passive"))
      (node (ref "IC4") (pin "8") (pinfunction "VS_8") (pintype "bidirectional"))
      (node (ref "R19") (pin "2") (pinfunction "2_2") (pintype "passive"))
    )
    (net (code "41") (name "Net-(IC5-VREF)") (class "Default")
      (node (ref "IC5") (pin "4") (pinfunction "VREF_4") (pintype "bidirectional"))
      (node (ref "R26") (pin "1") (pinfunction "1_1") (pintype "passive"))
      (node (ref "R27") (pin "1") (pinfunction "1_1") (pintype "passive"))
    )
    (net (code "42") (name "Net-(IC5-VS)") (class "Default")
      (node (ref "C15") (pin "2") (pinfunction "2_2") (pintype "passive"))
      (node (ref "C16") (pin "+") (pinfunction "+_+") (pintype "passive"))
      (node (ref "F5") (pin "1") (pinfunction "1_1") (pintype "passive"))
      (node (ref "IC5") (pin "8") (pinfunction "VS_8") (pintype "bidirectional"))
      (node (ref "R27") (pin "2") (pinfunction "2_2") (pintype "passive"))
    )
    (net (code "43") (name "Net-(IC6-XTAL1)") (class "Default")
      (node (ref "C20") (pin "2") (pinfunction "2_2") (pintype "passive"))
      (node (ref "IC6") (pin "8") (pinfunction "XTAL1_8") (pintype "input"))
      (node (ref "Q1") (pin "1") (pinfunction "1_1") (pintype "passive"))
    )
    (net (code "44") (name "Net-(IC6-XTAL2)") (class "Default")
      (node (ref "C21") (pin "2") (pinfunction "2_2") (pintype "passive"))
      (node (ref "IC6") (pin "7") (pinfunction "XTAL2_7") (pintype "output"))
      (node (ref "Q1") (pin "2") (pinfunction "2_2") (pintype "passive"))
    )
    (net (code "45") (name "Net-(IC7-VREF)") (class "Default")
      (node (ref "IC7") (pin "4") (pinfunction "VREF_4") (pintype "bidirectional"))
      (node (ref "R33") (pin "1") (pinfunction "1_1") (pintype "passive"))
      (node (ref "R34") (pin "1") (pinfunction "1_1") (pintype "passive"))
    )
    (net (code "46") (name "Net-(IC7-VS)") (class "Default")
      (node (ref "C24") (pin "+") (pinfunction "+_+") (pintype "passive"))
      (node (ref "C25") (pin "2") (pinfunction "2_2") (pintype "passive"))
      (node (ref "F6") (pin "1") (pinfunction "1_1") (pintype "passive"))
      (node (ref "IC7") (pin "8") (pinfunction "VS_8") (pintype "bidirectional"))
      (node (ref "R34") (pin "2") (pinfunction "2_2") (pintype "passive"))
    )
    (net (code "47") (name "Net-(IC8-VREF)") (class "Default")
      (node (ref "IC8") (pin "4") (pinfunction "VREF_4") (pintype "bidirectional"))
      (node (ref "R40") (pin "1") (pinfunction "1_1") (pintype "passive"))
      (node (ref "R41") (pin "1") (pinfunction "1_1") (pintype "passive"))
    )
    (net (code "48") (name "Net-(IC8-VS)") (class "Default")
      (node (ref "C29") (pin "+") (pinfunction "+_+") (pintype "passive"))
      (node (ref "C30") (pin "2") (pinfunction "2_2") (pintype "passive"))
      (node (ref "F9") (pin "1") (pinfunction "1_1") (pintype "passive"))
      (node (ref "IC8") (pin "8") (pinfunction "VS_8") (pintype "bidirectional"))
      (node (ref "R41") (pin "2") (pinfunction "2_2") (pintype "passive"))
    )
    (net (code "49") (name "Net-(IC9-VREF)") (class "Default")
      (node (ref "IC9") (pin "4") (pinfunction "VREF_4") (pintype "bidirectional"))
      (node (ref "R43") (pin "1") (pinfunction "1_1") (pintype "passive"))
      (node (ref "R44") (pin "1") (pinfunction "1_1") (pintype "passive"))
    )
    (net (code "50") (name "Net-(IC9-VS)") (class "Default")
      (node (ref "C27") (pin "+") (pinfunction "+_+") (pintype "passive"))
      (node (ref "C31") (pin "2") (pinfunction "2_2") (pintype "passive"))
      (node (ref "F8") (pin "1") (pinfunction "1_1") (pintype "passive"))
      (node (ref "IC9") (pin "8") (pinfunction "VS_8") (pintype "bidirectional"))
      (node (ref "R43") (pin "2") (pinfunction "2_2") (pintype "passive"))
    )
    (net (code "51") (name "Net-(LED1-C)") (class "Default")
      (node (ref "LED1") (pin "K") (pinfunction "C_K") (pintype "passive"))
      (node (ref "LED2") (pin "A") (pinfunction "A_A") (pintype "passive"))
      (node (ref "R9") (pin "2") (pinfunction "2_2") (pintype "passive"))
    )
    (net (code "52") (name "Net-(LED3-C)") (class "Default")
      (node (ref "LED3") (pin "K") (pinfunction "C_K") (pintype "passive"))
      (node (ref "LED4") (pin "A") (pinfunction "A_A") (pintype "passive"))
      (node (ref "R10") (pin "2") (pinfunction "2_2") (pintype "passive"))
    )
    (net (code "53") (name "Net-(LED5-C)") (class "Default")
      (node (ref "LED5") (pin "K") (pinfunction "C_K") (pintype "passive"))
      (node (ref "LED6") (pin "A") (pinfunction "A_A") (pintype "passive"))
      (node (ref "R22") (pin "2") (pinfunction "2_2") (pintype "passive"))
    )
    (net (code "54") (name "Net-(LED7-C)") (class "Default")
      (node (ref "LED7") (pin "K") (pinfunction "C_K") (pintype "passive"))
      (node (ref "LED8") (pin "A") (pinfunction "A_A") (pintype "passive"))
      (node (ref "R21") (pin "2") (pinfunction "2_2") (pintype "passive"))
    )
    (net (code "55") (name "Net-(LED9-C)") (class "Default")
      (node (ref "LED10") (pin "A") (pinfunction "A_A") (pintype "passive"))
      (node (ref "LED9") (pin "K") (pinfunction "C_K") (pintype "passive"))
      (node (ref "R29") (pin "2") (pinfunction "2_2") (pintype "passive"))
    )
    (net (code "56") (name "Net-(LED11-C)") (class "Default")
      (node (ref "LED11") (pin "K") (pinfunction "C_K") (pintype "passive"))
      (node (ref "LED12") (pin "A") (pinfunction "A_A") (pintype "passive"))
      (node (ref "R36") (pin "2") (pinfunction "2_2") (pintype "passive"))
    )
    (net (code "57") (name "Net-(LED13-C)") (class "Default")
      (node (ref "LED13") (pin "K") (pinfunction "C_K") (pintype "passive"))
      (node (ref "LED14") (pin "A") (pinfunction "A_A") (pintype "passive"))
      (node (ref "R47") (pin "2") (pinfunction "2_2") (pintype "passive"))
    )
    (net (code "58") (name "Net-(LED15-C)") (class "Default")
      (node (ref "LED15") (pin "K") (pinfunction "C_K") (pintype "passive"))
      (node (ref "LED16") (pin "A") (pinfunction "A_A") (pintype "passive"))
      (node (ref "R46") (pin "2") (pinfunction "2_2") (pintype "passive"))
    )
    (net (code "59") (name "OUT_A_0") (class "Default")
      (node (ref "IC4") (pin "5") (pinfunction "IN1_5") (pintype "bidirectional"))
      (node (ref "IC6") (pin "37") (pinfunction "(ADC0/PCINT0)PA0_37") (pintype "bidirectional"))
      (node (ref "R20") (pin "2") (pinfunction "2_2") (pintype "passive"))
    )
    (net (code "60") (name "OUT_A_1") (class "Default")
      (node (ref "IC4") (pin "6") (pinfunction "IN2_6") (pintype "bidirectional"))
      (node (ref "IC6") (pin "36") (pinfunction "(ADC1/PCINT1)PA1_36") (pintype "bidirectional"))
      (node (ref "R24") (pin "2") (pinfunction "2_2") (pintype "passive"))
    )
    (net (code "61") (name "OUT_B_0") (class "Default")
      (node (ref "IC1") (pin "5") (pinfunction "IN1_5") (pintype "bidirectional"))
      (node (ref "IC6") (pin "35") (pinfunction "(ADC2/PCINT2)PA2_35") (pintype "bidirectional"))
      (node (ref "R12") (pin "2") (pinfunction "2_2") (pintype "passive"))
    )
    (net (code "62") (name "OUT_B_1") (class "Default")
      (node (ref "IC1") (pin "6") (pinfunction "IN2_6") (pintype "bidirectional"))
      (node (ref "IC6") (pin "34") (pinfunction "(ADC3/PCINT3)PA3_34") (pintype "bidirectional"))
      (node (ref "R8") (pin "2") (pinfunction "2_2") (pintype "passive"))
    )
    (net (code "63") (name "OUT_C_0") (class "Default")
      (node (ref "IC2") (pin "5") (pinfunction "IN1_5") (pintype "bidirectional"))
      (node (ref "IC6") (pin "33") (pinfunction "(ADC4/PCINT4)PA4_33") (pintype "bidirectional"))
      (node (ref "R5") (pin "2") (pinfunction "2_2") (pintype "passive"))
    )
    (net (code "64") (name "OUT_C_1") (class "Default")
      (node (ref "IC2") (pin "6") (pinfunction "IN2_6") (pintype "bidirectional"))
      (node (ref "IC6") (pin "32") (pinfunction "(ADC5/PCINT5)PA5_32") (pintype "bidirectional"))
      (node (ref "R11") (pin "2") (pinfunction "2_2") (pintype "passive"))
    )
    (net (code "65") (name "OUT_D_0") (class "Default")
      (node (ref "IC3") (pin "5") (pinfunction "IN1_5") (pintype "bidirectional"))
      (node (ref "IC6") (pin "31") (pinfunction "(ADC6/PCINT6)PA6_31") (pintype "bidirectional"))
      (node (ref "R17") (pin "2") (pinfunction "2_2") (pintype "passive"))
    )
    (net (code "66") (name "OUT_D_1") (class "Default")
      (node (ref "IC3") (pin "6") (pinfunction "IN2_6") (pintype "bidirectional"))
      (node (ref "IC6") (pin "30") (pinfunction "(ADC7/PCINT7)PA7_30") (pintype "bidirectional"))
      (node (ref "R23") (pin "2") (pinfunction "2_2") (pintype "passive"))
    )
    (net (code "67") (name "OUT_E_0") (class "Default")
      (node (ref "IC6") (pin "9") (pinfunction "(RXD0/PCINT24)PD0_9") (pintype "bidirectional"))
      (node (ref "IC9") (pin "5") (pinfunction "IN1_5") (pintype "bidirectional"))
      (node (ref "R45") (pin "2") (pinfunction "2_2") (pintype "passive"))
    )
    (net (code "68") (name "OUT_E_1") (class "Default")
      (node (ref "IC6") (pin "10") (pinfunction "(TXD0/PCINT25)PD1_10") (pintype "bidirectional"))
      (node (ref "IC9") (pin "6") (pinfunction "IN2_6") (pintype "bidirectional"))
      (node (ref "R49") (pin "2") (pinfunction "2_2") (pintype "passive"))
    )
    (net (code "69") (name "OUT_F_0") (class "Default")
      (node (ref "IC6") (pin "11") (pinfunction "(RXD1/INT0/PCINT26)PD2_11") (pintype "bidirectional"))
      (node (ref "IC8") (pin "5") (pinfunction "IN1_5") (pintype "bidirectional"))
      (node (ref "R48") (pin "2") (pinfunction "2_2") (pintype "passive"))
    )
    (net (code "70") (name "OUT_F_1") (class "Default")
      (node (ref "IC6") (pin "12") (pinfunction "(TXD1/INT1/PCINT27)PD3_12") (pintype "bidirectional"))
      (node (ref "IC8") (pin "6") (pinfunction "IN2_6") (pintype "bidirectional"))
      (node (ref "R42") (pin "2") (pinfunction "2_2") (pintype "passive"))
    )
    (net (code "71") (name "OUT_G_0") (class "Default")
      (node (ref "IC6") (pin "13") (pinfunction "(XCK1/OC1B/PCINT28)PD4_13") (pintype "bidirectional"))
      (node (ref "IC7") (pin "5") (pinfunction "IN1_5") (pintype "bidirectional"))
      (node (ref "R37") (pin "2") (pinfunction "2_2") (pintype "passive"))
    )
    (net (code "72") (name "OUT_G_1") (class "Default")
      (node (ref "IC6") (pin "14") (pinfunction "(OC1A/PCINT29)PD5_14") (pintype "bidirectional"))
      (node (ref "IC7") (pin "6") (pinfunction "IN2_6") (pintype "bidirectional"))
      (node (ref "R35") (pin "2") (pinfunction "2_2") (pintype "passive"))
    )
    (net (code "73") (name "OUT_H_0") (class "Default")
      (node (ref "IC5") (pin "5") (pinfunction "IN1_5") (pintype "bidirectional"))
      (node (ref "IC6") (pin "15") (pinfunction "(OC2B/ICP/PCINT30)PD6_15") (pintype "bidirectional"))
      (node (ref "R30") (pin "2") (pinfunction "2_2") (pintype "passive"))
    )
    (net (code "74") (name "OUT_H_1") (class "Default")
      (node (ref "IC5") (pin "6") (pinfunction "IN2_6") (pintype "bidirectional"))
      (node (ref "IC6") (pin "16") (pinfunction "(OC2A/PCINT31)PD7_16") (pintype "bidirectional"))
      (node (ref "R28") (pin "2") (pinfunction "2_2") (pintype "passive"))
    )
    (net (code "75") (name "SCK") (class "Default")
      (node (ref "CONN") (pin "13") (pinfunction "13_SCK_13") (pintype "bidirectional"))
      (node (ref "IC6") (pin "3") (pinfunction "(SCK/PCINT15)PB7_3") (pintype "bidirectional"))
    )
    (net (code "76") (name "TCK") (class "Default")
      (node (ref "IC6") (pin "21") (pinfunction "(TCK/PCINT18)PC2_21") (pintype "bidirectional"))
      (node (ref "JP1") (pin "1") (pinfunction "1_1") (pintype "passive"))
    )
    (net (code "77") (name "TDI") (class "Default")
      (node (ref "IC6") (pin "24") (pinfunction "(TDI/PCINT21)PC5_24") (pintype "bidirectional"))
      (node (ref "JP1") (pin "9") (pinfunction "9_9") (pintype "passive"))
    )
    (net (code "78") (name "TDO") (class "Default")
      (node (ref "IC6") (pin "23") (pinfunction "(TDO/PCINT20)PC4_23") (pintype "bidirectional"))
      (node (ref "JP1") (pin "3") (pinfunction "3_3") (pintype "passive"))
    )
    (net (code "79") (name "TMS") (class "Default")
      (node (ref "IC6") (pin "22") (pinfunction "(TMS/PCINT19)PC3_22") (pintype "bidirectional"))
      (node (ref "JP1") (pin "5") (pinfunction "5_5") (pintype "passive"))
    )
    (net (code "80") (name "unconnected-(CONN-10_3.3V-Pad10)") (class "Default")
      (node (ref "CONN") (pin "10") (pinfunction "10_3.3V_10") (pintype "bidirectional"))
    )
    (net (code "81") (name "unconnected-(IC1-NC-Pad3)") (class "Default")
      (node (ref "IC1") (pin "3") (pinfunction "NC_3") (pintype "bidirectional"))
    )
    (net (code "82") (name "unconnected-(IC1-NC2-Pad9)") (class "Default")
      (node (ref "IC1") (pin "9") (pinfunction "NC2_9") (pintype "bidirectional"))
    )
    (net (code "83") (name "unconnected-(IC2-NC-Pad3)") (class "Default")
      (node (ref "IC2") (pin "3") (pinfunction "NC_3") (pintype "bidirectional"))
    )
    (net (code "84") (name "unconnected-(IC2-NC2-Pad9)") (class "Default")
      (node (ref "IC2") (pin "9") (pinfunction "NC2_9") (pintype "bidirectional"))
    )
    (net (code "85") (name "unconnected-(IC3-NC-Pad3)") (class "Default")
      (node (ref "IC3") (pin "3") (pinfunction "NC_3") (pintype "bidirectional"))
    )
    (net (code "86") (name "unconnected-(IC3-NC2-Pad9)") (class "Default")
      (node (ref "IC3") (pin "9") (pinfunction "NC2_9") (pintype "bidirectional"))
    )
    (net (code "87") (name "unconnected-(IC4-NC-Pad3)") (class "Default")
      (node (ref "IC4") (pin "3") (pinfunction "NC_3") (pintype "bidirectional"))
    )
    (net (code "88") (name "unconnected-(IC4-NC2-Pad9)") (class "Default")
      (node (ref "IC4") (pin "9") (pinfunction "NC2_9") (pintype "bidirectional"))
    )
    (net (code "89") (name "unconnected-(IC5-NC-Pad3)") (class "Default")
      (node (ref "IC5") (pin "3") (pinfunction "NC_3") (pintype "bidirectional"))
    )
    (net (code "90") (name "unconnected-(IC5-NC2-Pad9)") (class "Default")
      (node (ref "IC5") (pin "9") (pinfunction "NC2_9") (pintype "bidirectional"))
    )
    (net (code "91") (name "unconnected-(IC6-(CLKO{slash}T1{slash}PCINT9)PB1-Pad41)") (class "Default")
      (node (ref "IC6") (pin "41") (pinfunction "(CLKO/T1/PCINT9)PB1_41") (pintype "bidirectional"))
    )
    (net (code "92") (name "unconnected-(IC6-(INT2{slash}AIN0{slash}PCINT10)PB2-Pad42)") (class "Default")
      (node (ref "IC6") (pin "42") (pinfunction "(INT2/AIN0/PCINT10)PB2_42") (pintype "bidirectional"))
    )
    (net (code "93") (name "unconnected-(IC6-(OC0A{slash}AIN1{slash}PCINT11)PB3-Pad43)") (class "Default")
      (node (ref "IC6") (pin "43") (pinfunction "(OC0A/AIN1/PCINT11)PB3_43") (pintype "bidirectional"))
    )
    (net (code "94") (name "unconnected-(IC6-(SCL{slash}PCINT16)PC0-Pad19)") (class "Default")
      (node (ref "IC6") (pin "19") (pinfunction "(SCL/PCINT16)PC0_19") (pintype "bidirectional"))
    )
    (net (code "95") (name "unconnected-(IC6-(SDA{slash}PCINT17)PC1-Pad20)") (class "Default")
      (node (ref "IC6") (pin "20") (pinfunction "(SDA/PCINT17)PC1_20") (pintype "bidirectional"))
    )
    (net (code "96") (name "unconnected-(IC6-(TOSC1{slash}PCINT22)PC6-Pad25)") (class "Default")
      (node (ref "IC6") (pin "25") (pinfunction "(TOSC1/PCINT22)PC6_25") (pintype "bidirectional"))
    )
    (net (code "97") (name "unconnected-(IC6-(TOSC2{slash}PCINT23)PC7-Pad26)") (class "Default")
      (node (ref "IC6") (pin "26") (pinfunction "(TOSC2/PCINT23)PC7_26") (pintype "bidirectional"))
    )
    (net (code "98") (name "unconnected-(IC6-(XCK0{slash}T0{slash}PCINT8)PB0-Pad40)") (class "Default")
      (node (ref "IC6") (pin "40") (pinfunction "(XCK0/T0/PCINT8)PB0_40") (pintype "bidirectional"))
    )
    (net (code "99") (name "unconnected-(IC7-NC-Pad3)") (class "Default")
      (node (ref "IC7") (pin "3") (pinfunction "NC_3") (pintype "bidirectional"))
    )
    (net (code "100") (name "unconnected-(IC7-NC2-Pad9)") (class "Default")
      (node (ref "IC7") (pin "9") (pinfunction "NC2_9") (pintype "bidirectional"))
    )
    (net (code "101") (name "unconnected-(IC8-NC-Pad3)") (class "Default")
      (node (ref "IC8") (pin "3") (pinfunction "NC_3") (pintype "bidirectional"))
    )
    (net (code "102") (name "unconnected-(IC8-NC2-Pad9)") (class "Default")
      (node (ref "IC8") (pin "9") (pinfunction "NC2_9") (pintype "bidirectional"))
    )
    (net (code "103") (name "unconnected-(IC9-NC-Pad3)") (class "Default")
      (node (ref "IC9") (pin "3") (pinfunction "NC_3") (pintype "bidirectional"))
    )
    (net (code "104") (name "unconnected-(IC9-NC2-Pad9)") (class "Default")
      (node (ref "IC9") (pin "9") (pinfunction "NC2_9") (pintype "bidirectional"))
    )
    (net (code "105") (name "unconnected-(JP1-Pad8)") (class "Default")
      (node (ref "JP1") (pin "8") (pinfunction "8_8") (pintype "passive"))
    )
  )
)
